# core-debug.net
KiCad netlist of a schematic drawn in EAGLE
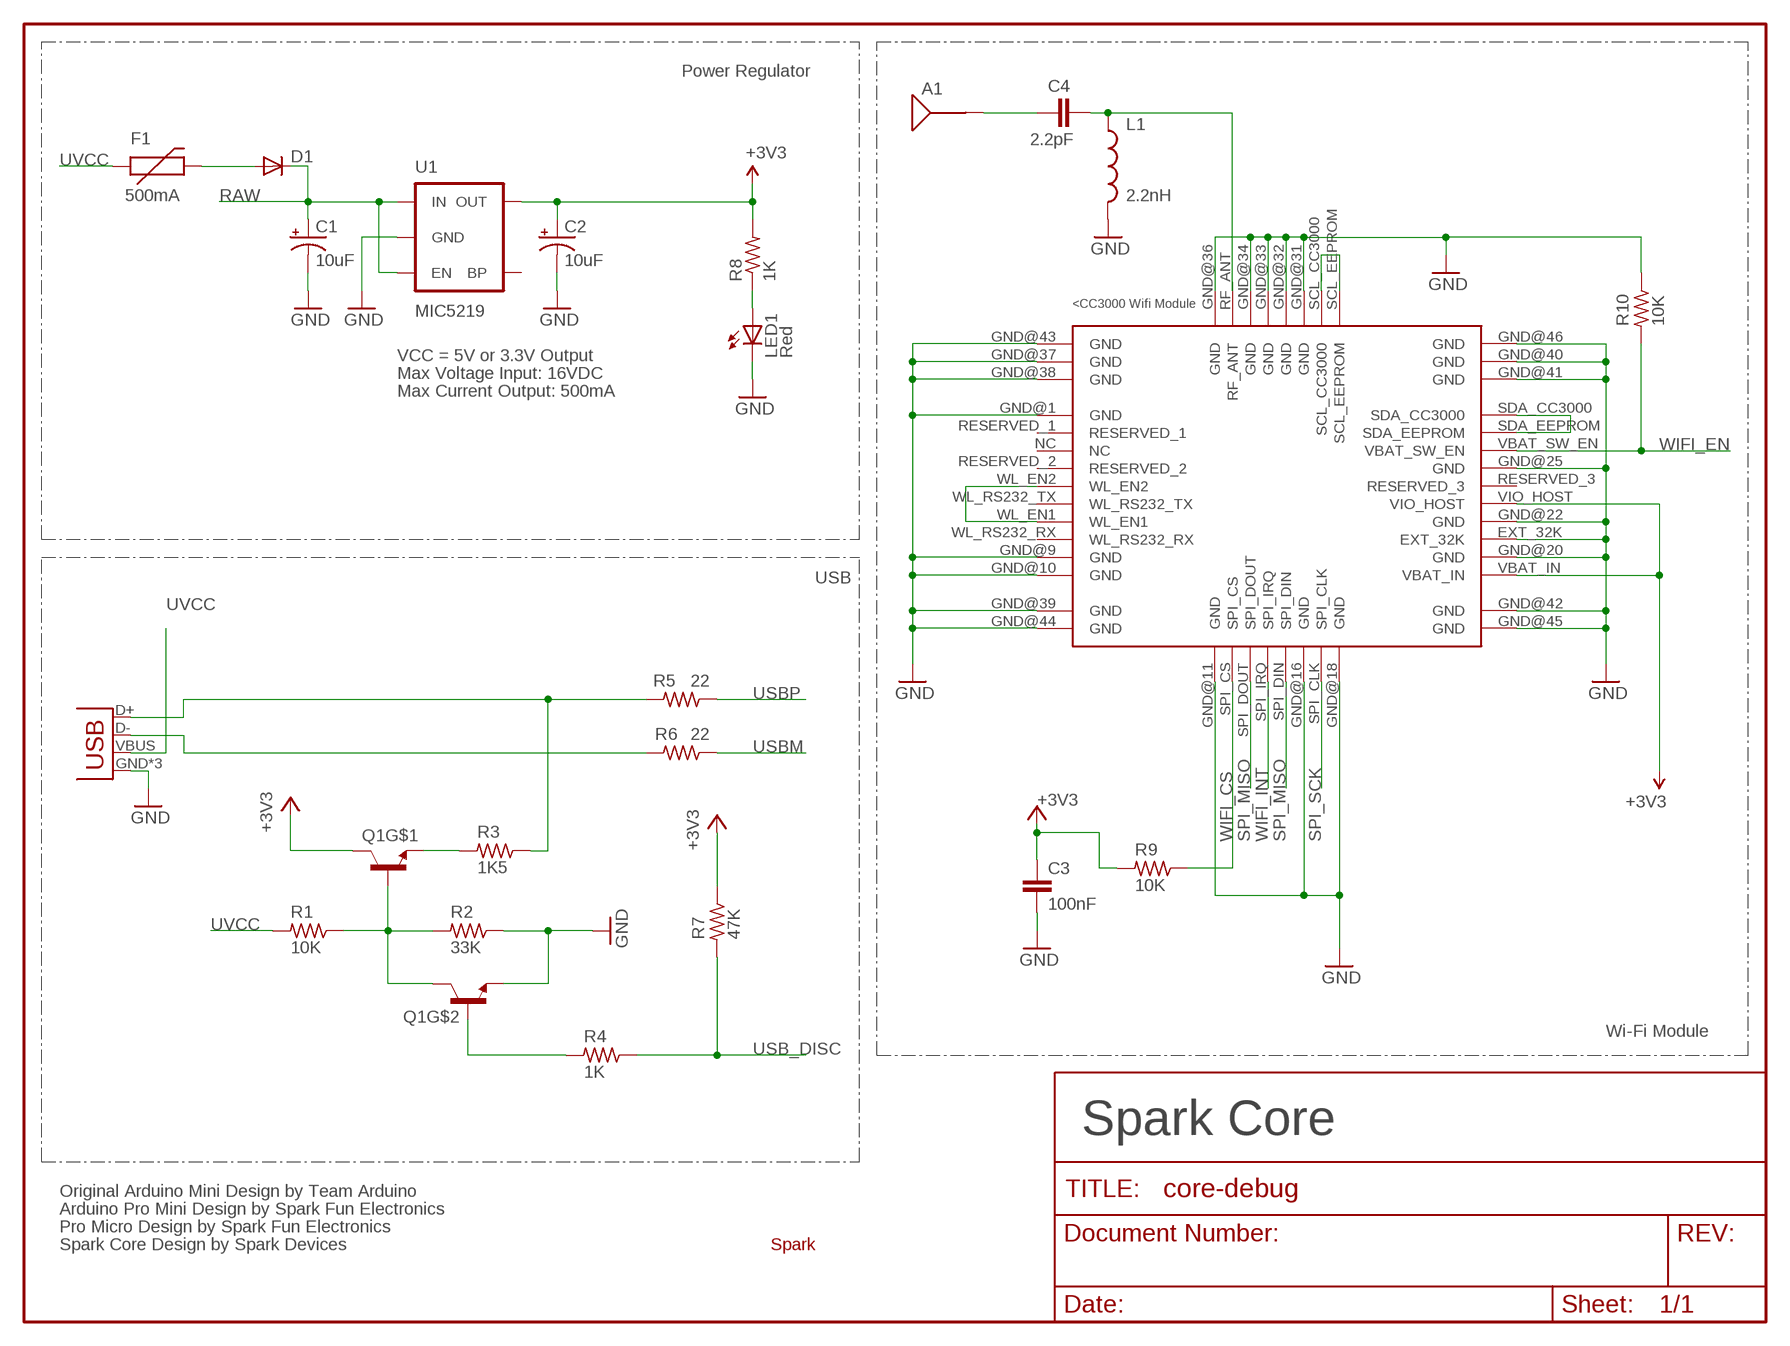
[diagram p0: schematic, sheet 1, part 1 of 2]
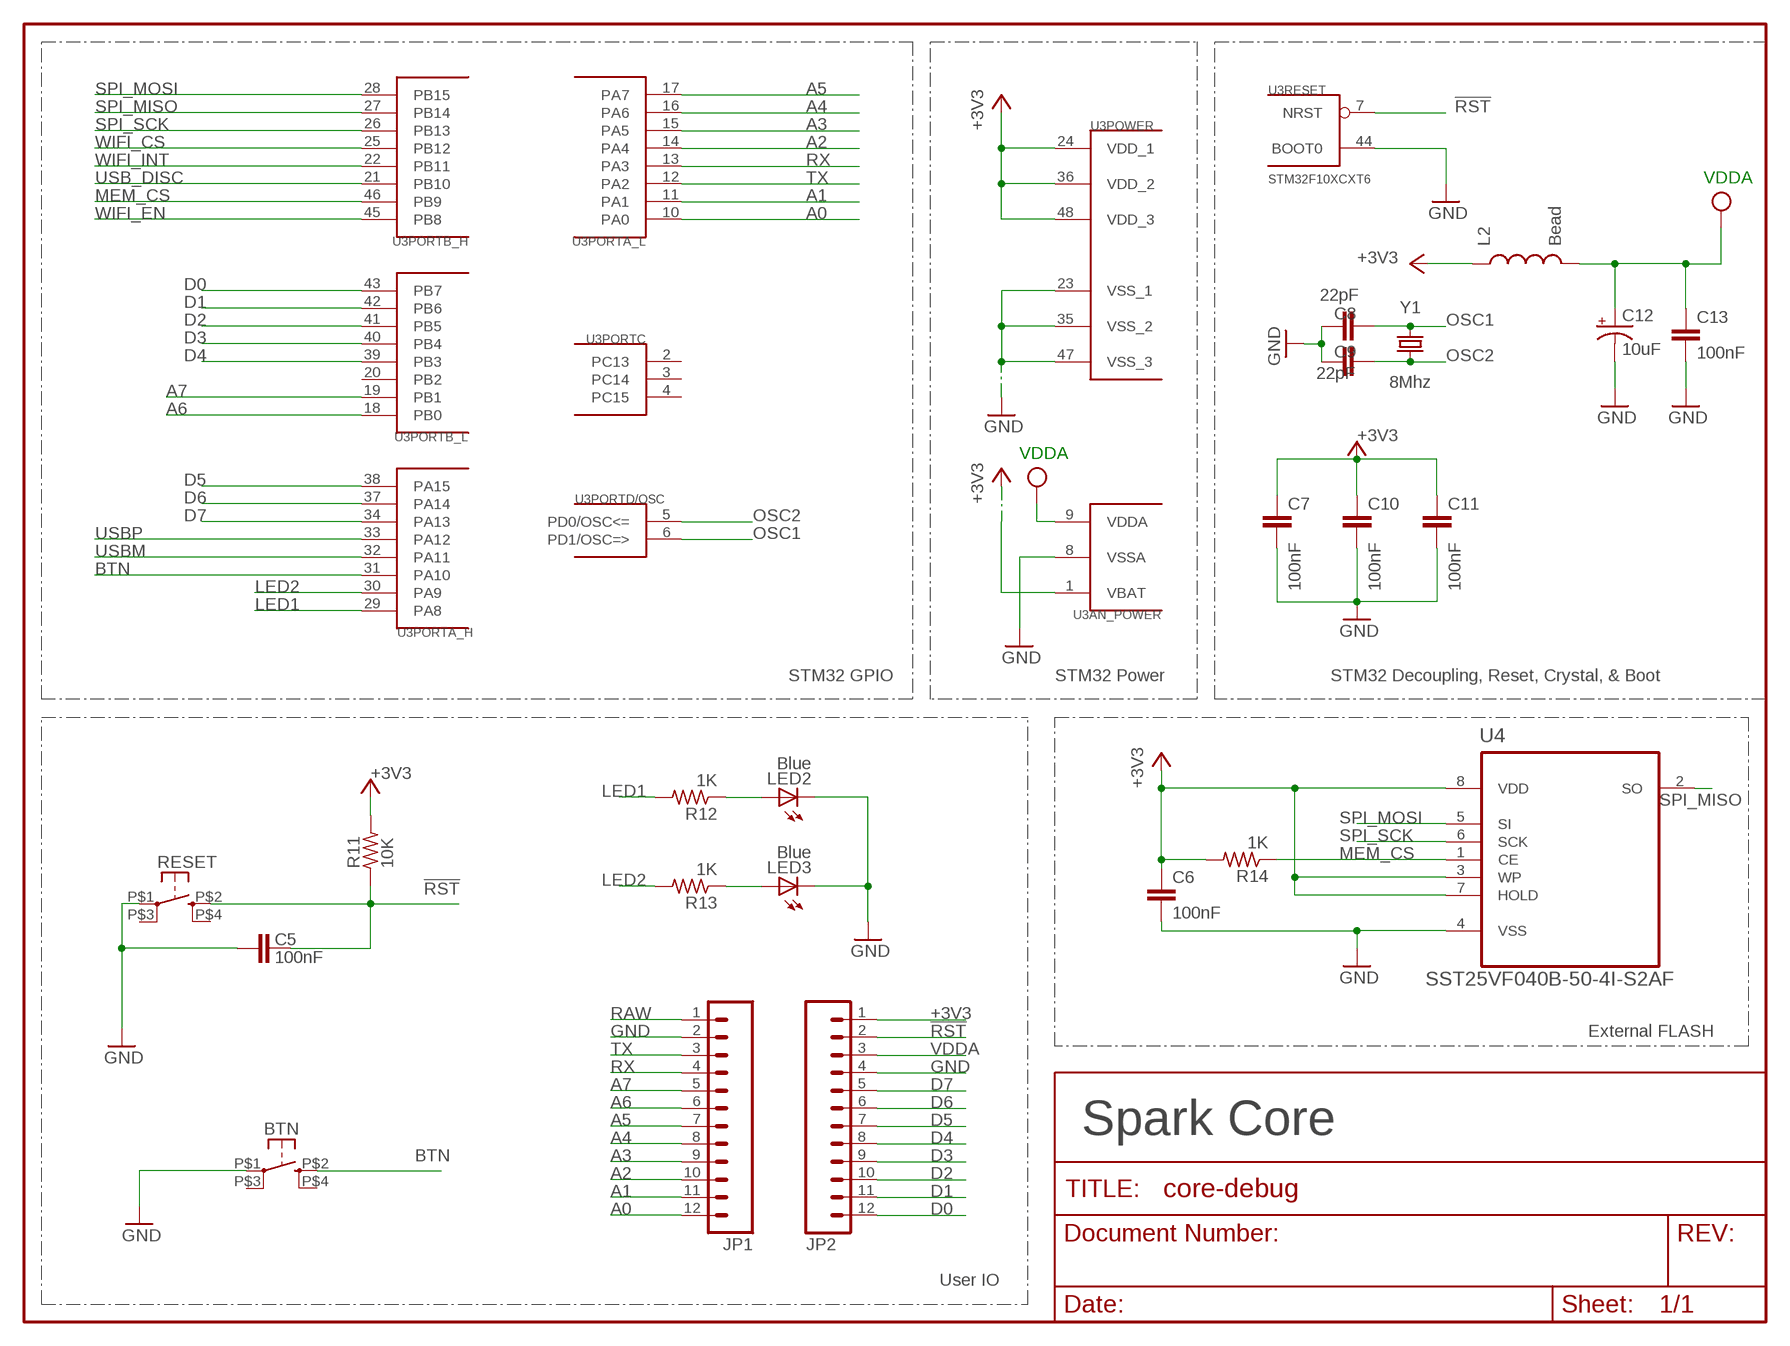
[diagram p1: schematic, sheet 1, part 2 of 2]

(export (version "E")
  (design (tool "Eeschema 10.0.6"))
  (components
    (comp (ref "A1")
      (value "ANTENNA2SMD5")
      (footprint "eagle-import:ANTENNA-CHIP5")
      (libsource (lib "eagle-import") (part "ANTENNA2SMD5"))
    )
    (comp (ref "BTN")
      (value "KMR211GLFS")
      (footprint "eagle-import:PUSHBUTTON-KMR241GLFS")
      (libsource (lib "eagle-import") (part "BUTTON-KMR241GLFS"))
    )
    (comp (ref "C1")
      (value "10uF")
      (footprint "eagle-import:EIA3216")
      (libsource (lib "eagle-import") (part "CAP_POL1206"))
    )
    (comp (ref "C2")
      (value "10uF")
      (footprint "eagle-import:EIA3216")
      (libsource (lib "eagle-import") (part "CAP_POL1206"))
    )
    (comp (ref "C3")
      (value "100nF")
      (footprint "eagle-import:C0603")
      (libsource (lib "eagle-import") (part "C-EUC0603"))
    )
    (comp (ref "C4")
      (value "2.2pF")
      (footprint "eagle-import:C0603")
      (libsource (lib "eagle-import") (part "C-EUC0603"))
    )
    (comp (ref "C5")
      (value "100nF")
      (footprint "eagle-import:C0603")
      (libsource (lib "eagle-import") (part "C-EUC0603"))
    )
    (comp (ref "C6")
      (value "100nF")
      (footprint "eagle-import:C0603")
      (libsource (lib "eagle-import") (part "C-EUC0603"))
    )
    (comp (ref "C7")
      (value "100nF")
      (footprint "eagle-import:C0603")
      (libsource (lib "eagle-import") (part "C-EUC0603"))
    )
    (comp (ref "C8")
      (value "22pF")
      (footprint "eagle-import:C0603")
      (libsource (lib "eagle-import") (part "C-EUC0603"))
    )
    (comp (ref "C9")
      (value "22pF")
      (footprint "eagle-import:C0603")
      (libsource (lib "eagle-import") (part "C-EUC0603"))
    )
    (comp (ref "C10")
      (value "100nF")
      (footprint "eagle-import:C0603")
      (libsource (lib "eagle-import") (part "C-EUC0603"))
    )
    (comp (ref "C11")
      (value "100nF")
      (footprint "eagle-import:C0603")
      (libsource (lib "eagle-import") (part "C-EUC0603"))
    )
    (comp (ref "C12")
      (value "10uF")
      (footprint "eagle-import:EIA3216")
      (libsource (lib "eagle-import") (part "CAP_POL1206"))
    )
    (comp (ref "C13")
      (value "100nF")
      (footprint "eagle-import:C0603")
      (libsource (lib "eagle-import") (part "C-EUC0603"))
    )
    (comp (ref "D1")
      (value "DIODESOD")
      (footprint "eagle-import:SOD-323")
      (libsource (lib "eagle-import") (part "DIODESOD"))
    )
    (comp (ref "F1")
      (value "500mA")
      (footprint "eagle-import:PTC-1206")
      (libsource (lib "eagle-import") (part "PTCSMD"))
    )
    (comp (ref "JP1")
      (value "M12PTH")
      (footprint "eagle-import:1X12")
      (libsource (lib "eagle-import") (part "M12PTH"))
    )
    (comp (ref "JP2")
      (value "M12PTH")
      (footprint "eagle-import:1X12")
      (libsource (lib "eagle-import") (part "M12PTH"))
    )
    (comp (ref "L1")
      (value "2.2nH")
      (footprint "eagle-import:0603")
      (libsource (lib "eagle-import") (part "INDUCTOR0603"))
    )
    (comp (ref "L2")
      (value "Bead")
      (footprint "eagle-import:0603")
      (libsource (lib "eagle-import") (part "INDUCTOR0603"))
    )
    (comp (ref "LED1")
      (value "Red")
      (footprint "eagle-import:LED-0603")
      (libsource (lib "eagle-import") (part "LED0603"))
    )
    (comp (ref "LED2")
      (value "Blue")
      (footprint "eagle-import:LED-0603")
      (libsource (lib "eagle-import") (part "LED0603"))
    )
    (comp (ref "LED3")
      (value "Blue")
      (footprint "eagle-import:LED-0603")
      (libsource (lib "eagle-import") (part "LED0603"))
    )
    (comp (ref "Q1")
      (value "MMDT3904")
      (footprint "eagle-import:SOT363")
      (libsource (lib "eagle-import") (part "MMDT3904"))
    )
    (comp (ref "R1")
      (value "10K")
      (footprint "eagle-import:R0603")
      (libsource (lib "eagle-import") (part "R-US_R0603"))
    )
    (comp (ref "R2")
      (value "33K")
      (footprint "eagle-import:R0603")
      (libsource (lib "eagle-import") (part "R-US_R0603"))
    )
    (comp (ref "R3")
      (value "1K5")
      (footprint "eagle-import:R0603")
      (libsource (lib "eagle-import") (part "R-US_R0603"))
    )
    (comp (ref "R4")
      (value "1K")
      (footprint "eagle-import:R0603")
      (libsource (lib "eagle-import") (part "R-US_R0603"))
    )
    (comp (ref "R5")
      (value "22")
      (footprint "eagle-import:R0603")
      (libsource (lib "eagle-import") (part "R-US_R0603"))
    )
    (comp (ref "R6")
      (value "22")
      (footprint "eagle-import:R0603")
      (libsource (lib "eagle-import") (part "R-US_R0603"))
    )
    (comp (ref "R7")
      (value "47K")
      (footprint "eagle-import:R0603")
      (libsource (lib "eagle-import") (part "R-US_R0603"))
    )
    (comp (ref "R8")
      (value "1K")
      (footprint "eagle-import:R0603")
      (libsource (lib "eagle-import") (part "R-US_R0603"))
    )
    (comp (ref "R9")
      (value "10K")
      (footprint "eagle-import:R0603")
      (libsource (lib "eagle-import") (part "R-US_R0603"))
    )
    (comp (ref "R10")
      (value "10K")
      (footprint "eagle-import:R0603")
      (libsource (lib "eagle-import") (part "R-US_R0603"))
    )
    (comp (ref "R11")
      (value "10K")
      (footprint "eagle-import:R0603")
      (libsource (lib "eagle-import") (part "R-US_R0603"))
    )
    (comp (ref "R12")
      (value "1K")
      (footprint "eagle-import:R0603")
      (libsource (lib "eagle-import") (part "R-US_R0603"))
    )
    (comp (ref "R13")
      (value "1K")
      (footprint "eagle-import:R0603")
      (libsource (lib "eagle-import") (part "R-US_R0603"))
    )
    (comp (ref "R14")
      (value "1K")
      (footprint "eagle-import:R0603")
      (libsource (lib "eagle-import") (part "R-US_R0603"))
    )
    (comp (ref "RESET")
      (value "KMR211GLFS")
      (footprint "eagle-import:PUSHBUTTON-KMR241GLFS")
      (libsource (lib "eagle-import") (part "BUTTON-KMR241GLFS"))
    )
    (comp (ref "U$1")
      (value "SPARK_LOGO2")
      (footprint "eagle-import:SPARK_LOGO2")
      (libsource (lib "eagle-import") (part "SPARK_LOGO2"))
    )
    (comp (ref "U1")
      (value "MIC5219")
      (footprint "eagle-import:SOT23-5")
      (libsource (lib "eagle-import") (part "V_REG_LDOSMD"))
    )
    (comp (ref "U2")
      (value "CC3000")
      (footprint "eagle-import:CC3000")
      (libsource (lib "eagle-import") (part "CC3000"))
    )
    (comp (ref "U3")
      (value "STM32F10XCXT6")
      (footprint "eagle-import:TQFP48")
      (libsource (lib "eagle-import") (part "STM32F10XCXT6"))
    )
    (comp (ref "U4")
      (value "SST25VF040B-50-4I-S2AF")
      (footprint "eagle-import:SOIC127P790X216-8N")
      (libsource (lib "eagle-import") (part "SST25VF040B-50-4I-S2AF"))
    )
    (comp (ref "X1")
      (value "USB-MICROB")
      (footprint "eagle-import:USB-MICROB")
      (libsource (lib "eagle-import") (part "USB-MICROB"))
    )
    (comp (ref "Y1")
      (value "8Mhz")
      (footprint "eagle-import:CRYSTAL-SMD-5X3")
      (libsource (lib "eagle-import") (part "CRYSTAL5X3"))
    )
  )
  (nets
    (net (code "1") (name "+3V3") (class "Default")
      (node (ref "C10") (pin "1") (pinfunction "1_1") (pintype "passive"))
      (node (ref "C11") (pin "1") (pinfunction "1_1") (pintype "passive"))
      (node (ref "C2") (pin "A") (pinfunction "+_A") (pintype "passive"))
      (node (ref "C3") (pin "1") (pinfunction "1_1") (pintype "passive"))
      (node (ref "C6") (pin "1") (pinfunction "1_1") (pintype "passive"))
      (node (ref "C7") (pin "1") (pinfunction "1_1") (pintype "passive"))
      (node (ref "JP2") (pin "1") (pinfunction "1_1") (pintype "passive"))
      (node (ref "L2") (pin "1") (pinfunction "1_1") (pintype "passive"))
      (node (ref "Q1") (pin "3") (pinfunction "C_3") (pintype "passive"))
      (node (ref "R11") (pin "2") (pinfunction "2_2") (pintype "passive"))
      (node (ref "R14") (pin "2") (pinfunction "2_2") (pintype "passive"))
      (node (ref "R7") (pin "1") (pinfunction "1_1") (pintype "passive"))
      (node (ref "R8") (pin "2") (pinfunction "2_2") (pintype "passive"))
      (node (ref "R9") (pin "2") (pinfunction "2_2") (pintype "passive"))
      (node (ref "U1") (pin "5") (pinfunction "OUT_5") (pintype "passive"))
      (node (ref "U2") (pin "VBAT_IN") (pinfunction "VBAT_IN_VBAT_IN") (pintype "power_in"))
      (node (ref "U2") (pin "VIO_HOST") (pinfunction "VIO_HOST_VIO_HOST") (pintype "power_in"))
      (node (ref "U3") (pin "1") (pinfunction "VBAT_1") (pintype "power_in"))
      (node (ref "U3") (pin "24") (pinfunction "VDD_1_24") (pintype "power_in"))
      (node (ref "U3") (pin "36") (pinfunction "VDD_2_36") (pintype "power_in"))
      (node (ref "U3") (pin "48") (pinfunction "VDD_3_48") (pintype "power_in"))
      (node (ref "U4") (pin "3") (pinfunction "WP_3") (pintype "input"))
      (node (ref "U4") (pin "7") (pinfunction "HOLD_7") (pintype "input"))
      (node (ref "U4") (pin "8") (pinfunction "VDD_8") (pintype "power_in"))
    )
    (net (code "2") (name "/A0") (class "Default")
      (node (ref "JP1") (pin "12") (pinfunction "12_12") (pintype "passive"))
      (node (ref "U3") (pin "10") (pinfunction "PA0_10") (pintype "bidirectional"))
    )
    (net (code "3") (name "/A1") (class "Default")
      (node (ref "JP1") (pin "11") (pinfunction "11_11") (pintype "passive"))
      (node (ref "U3") (pin "11") (pinfunction "PA1_11") (pintype "bidirectional"))
    )
    (net (code "4") (name "/A2") (class "Default")
      (node (ref "JP1") (pin "10") (pinfunction "10_10") (pintype "passive"))
      (node (ref "U3") (pin "14") (pinfunction "PA4_14") (pintype "bidirectional"))
    )
    (net (code "5") (name "/A3") (class "Default")
      (node (ref "JP1") (pin "9") (pinfunction "9_9") (pintype "passive"))
      (node (ref "U3") (pin "15") (pinfunction "PA5_15") (pintype "bidirectional"))
    )
    (net (code "6") (name "/A4") (class "Default")
      (node (ref "JP1") (pin "8") (pinfunction "8_8") (pintype "passive"))
      (node (ref "U3") (pin "16") (pinfunction "PA6_16") (pintype "bidirectional"))
    )
    (net (code "7") (name "/A5") (class "Default")
      (node (ref "JP1") (pin "7") (pinfunction "7_7") (pintype "passive"))
      (node (ref "U3") (pin "17") (pinfunction "PA7_17") (pintype "bidirectional"))
    )
    (net (code "8") (name "/A6") (class "Default")
      (node (ref "JP1") (pin "6") (pinfunction "6_6") (pintype "passive"))
      (node (ref "U3") (pin "18") (pinfunction "PB0_18") (pintype "bidirectional"))
    )
    (net (code "9") (name "/A7") (class "Default")
      (node (ref "JP1") (pin "5") (pinfunction "5_5") (pintype "passive"))
      (node (ref "U3") (pin "19") (pinfunction "PB1_19") (pintype "bidirectional"))
    )
    (net (code "10") (name "/BTN") (class "Default")
      (node (ref "BTN") (pin "P$2") (pinfunction "2_P$2") (pintype "passive"))
      (node (ref "U3") (pin "31") (pinfunction "PA10_31") (pintype "bidirectional"))
    )
    (net (code "11") (name "/D0") (class "Default")
      (node (ref "JP2") (pin "12") (pinfunction "12_12") (pintype "passive"))
      (node (ref "U3") (pin "43") (pinfunction "PB7_43") (pintype "bidirectional"))
    )
    (net (code "12") (name "/D1") (class "Default")
      (node (ref "JP2") (pin "11") (pinfunction "11_11") (pintype "passive"))
      (node (ref "U3") (pin "42") (pinfunction "PB6_42") (pintype "bidirectional"))
    )
    (net (code "13") (name "/D2") (class "Default")
      (node (ref "JP2") (pin "10") (pinfunction "10_10") (pintype "passive"))
      (node (ref "U3") (pin "41") (pinfunction "PB5_41") (pintype "bidirectional"))
    )
    (net (code "14") (name "/D3") (class "Default")
      (node (ref "JP2") (pin "9") (pinfunction "9_9") (pintype "passive"))
      (node (ref "U3") (pin "40") (pinfunction "PB4_40") (pintype "bidirectional"))
    )
    (net (code "15") (name "/D4") (class "Default")
      (node (ref "JP2") (pin "8") (pinfunction "8_8") (pintype "passive"))
      (node (ref "U3") (pin "39") (pinfunction "PB3_39") (pintype "bidirectional"))
    )
    (net (code "16") (name "/D5") (class "Default")
      (node (ref "JP2") (pin "7") (pinfunction "7_7") (pintype "passive"))
      (node (ref "U3") (pin "38") (pinfunction "PA15_38") (pintype "bidirectional"))
    )
    (net (code "17") (name "/D6") (class "Default")
      (node (ref "JP2") (pin "6") (pinfunction "6_6") (pintype "passive"))
      (node (ref "U3") (pin "37") (pinfunction "PA14_37") (pintype "bidirectional"))
    )
    (net (code "18") (name "/D7") (class "Default")
      (node (ref "JP2") (pin "5") (pinfunction "5_5") (pintype "passive"))
      (node (ref "U3") (pin "34") (pinfunction "PA13_34") (pintype "bidirectional"))
    )
    (net (code "19") (name "/LED1") (class "Default")
      (node (ref "R12") (pin "2") (pinfunction "2_2") (pintype "passive"))
      (node (ref "U3") (pin "29") (pinfunction "PA8_29") (pintype "bidirectional"))
    )
    (net (code "20") (name "/LED2") (class "Default")
      (node (ref "R13") (pin "2") (pinfunction "2_2") (pintype "passive"))
      (node (ref "U3") (pin "30") (pinfunction "PA9_30") (pintype "bidirectional"))
    )
    (net (code "21") (name "/MEM_CS") (class "Default")
      (node (ref "R14") (pin "1") (pinfunction "1_1") (pintype "passive"))
      (node (ref "U3") (pin "46") (pinfunction "PB9_46") (pintype "bidirectional"))
      (node (ref "U4") (pin "1") (pinfunction "CE_1") (pintype "input"))
    )
    (net (code "22") (name "/OSC1") (class "Default")
      (node (ref "C8") (pin "1") (pinfunction "1_1") (pintype "passive"))
      (node (ref "U3") (pin "6") (pinfunction "PD1/OSC=>_6") (pintype "bidirectional"))
      (node (ref "Y1") (pin "3") (pinfunction "2_3") (pintype "passive"))
    )
    (net (code "23") (name "/OSC2") (class "Default")
      (node (ref "C9") (pin "1") (pinfunction "1_1") (pintype "passive"))
      (node (ref "U3") (pin "5") (pinfunction "PD0/OSC<=_5") (pintype "bidirectional"))
      (node (ref "Y1") (pin "1") (pinfunction "1_1") (pintype "passive"))
    )
    (net (code "24") (name "/RAW") (class "Default")
      (node (ref "C1") (pin "A") (pinfunction "+_A") (pintype "passive"))
      (node (ref "D1") (pin "1") (pinfunction "C_1") (pintype "passive"))
      (node (ref "JP1") (pin "1") (pinfunction "1_1") (pintype "passive"))
      (node (ref "U1") (pin "1") (pinfunction "IN_1") (pintype "input"))
      (node (ref "U1") (pin "3") (pinfunction "EN_3") (pintype "input"))
    )
    (net (code "25") (name "/RX") (class "Default")
      (node (ref "JP1") (pin "4") (pinfunction "4_4") (pintype "passive"))
      (node (ref "U3") (pin "13") (pinfunction "PA3_13") (pintype "bidirectional"))
    )
    (net (code "26") (name "/SPI_MISO") (class "Default")
      (node (ref "U2") (pin "SPI_DIN") (pinfunction "SPI_DIN_SPI_DIN") (pintype "input"))
      (node (ref "U2") (pin "SPI_DOUT") (pinfunction "SPI_DOUT_SPI_DOUT") (pintype "output"))
      (node (ref "U3") (pin "27") (pinfunction "PB14_27") (pintype "bidirectional"))
      (node (ref "U4") (pin "2") (pinfunction "SO_2") (pintype "output"))
    )
    (net (code "27") (name "/SPI_MOSI") (class "Default")
      (node (ref "U3") (pin "28") (pinfunction "PB15_28") (pintype "bidirectional"))
      (node (ref "U4") (pin "5") (pinfunction "SI_5") (pintype "input"))
    )
    (net (code "28") (name "/SPI_SCK") (class "Default")
      (node (ref "U2") (pin "SPI_CLK") (pinfunction "SPI_CLK_SPI_CLK") (pintype "input"))
      (node (ref "U3") (pin "26") (pinfunction "PB13_26") (pintype "bidirectional"))
      (node (ref "U4") (pin "6") (pinfunction "SCK_6") (pintype "input"))
    )
    (net (code "29") (name "/TX") (class "Default")
      (node (ref "JP1") (pin "3") (pinfunction "3_3") (pintype "passive"))
      (node (ref "U3") (pin "12") (pinfunction "PA2_12") (pintype "bidirectional"))
    )
    (net (code "30") (name "/USBM") (class "Default")
      (node (ref "R6") (pin "1") (pinfunction "1_1") (pintype "passive"))
      (node (ref "U3") (pin "32") (pinfunction "PA11_32") (pintype "bidirectional"))
    )
    (net (code "31") (name "/USBP") (class "Default")
      (node (ref "R5") (pin "1") (pinfunction "1_1") (pintype "passive"))
      (node (ref "U3") (pin "33") (pinfunction "PA12_33") (pintype "bidirectional"))
    )
    (net (code "32") (name "/USB_DISC") (class "Default")
      (node (ref "R4") (pin "1") (pinfunction "1_1") (pintype "passive"))
      (node (ref "R7") (pin "2") (pinfunction "2_2") (pintype "passive"))
      (node (ref "U3") (pin "21") (pinfunction "PB10_21") (pintype "bidirectional"))
    )
    (net (code "33") (name "/UVCC") (class "Default")
      (node (ref "F1") (pin "1") (pinfunction "1_1") (pintype "bidirectional"))
      (node (ref "R1") (pin "2") (pinfunction "2_2") (pintype "passive"))
      (node (ref "X1") (pin "VBUS") (pinfunction "VBUS_VBUS") (pintype "bidirectional"))
    )
    (net (code "34") (name "/WIFI_CS") (class "Default")
      (node (ref "R9") (pin "1") (pinfunction "1_1") (pintype "passive"))
      (node (ref "U2") (pin "SPI_CS") (pinfunction "SPI_CS_SPI_CS") (pintype "input"))
      (node (ref "U3") (pin "25") (pinfunction "PB12_25") (pintype "bidirectional"))
    )
    (net (code "35") (name "/WIFI_EN") (class "Default")
      (node (ref "R10") (pin "2") (pinfunction "2_2") (pintype "passive"))
      (node (ref "U2") (pin "VBAT_SW_EN") (pinfunction "VBAT_SW_EN_VBAT_SW_EN") (pintype "input"))
      (node (ref "U3") (pin "45") (pinfunction "PB8_45") (pintype "bidirectional"))
    )
    (net (code "36") (name "/WIFI_INT") (class "Default")
      (node (ref "U2") (pin "SPI_IRQ") (pinfunction "SPI_IRQ_SPI_IRQ") (pintype "output"))
      (node (ref "U3") (pin "22") (pinfunction "PB11_22") (pintype "bidirectional"))
    )
    (net (code "37") (name "/~{RST}") (class "Default")
      (node (ref "C5") (pin "2") (pinfunction "2_2") (pintype "passive"))
      (node (ref "JP2") (pin "2") (pinfunction "2_2") (pintype "passive"))
      (node (ref "R11") (pin "1") (pinfunction "1_1") (pintype "passive"))
      (node (ref "RESET") (pin "P$2") (pinfunction "2_P$2") (pintype "passive"))
      (node (ref "U3") (pin "7") (pinfunction "NRST_7") (pintype "input"))
    )
    (net (code "38") (name "GND") (class "Default")
      (node (ref "BTN") (pin "P$1") (pinfunction "1_P$1") (pintype "passive"))
      (node (ref "C1") (pin "C") (pinfunction "-_C") (pintype "passive"))
      (node (ref "C10") (pin "2") (pinfunction "2_2") (pintype "passive"))
      (node (ref "C11") (pin "2") (pinfunction "2_2") (pintype "passive"))
      (node (ref "C12") (pin "C") (pinfunction "-_C") (pintype "passive"))
      (node (ref "C13") (pin "2") (pinfunction "2_2") (pintype "passive"))
      (node (ref "C2") (pin "C") (pinfunction "-_C") (pintype "passive"))
      (node (ref "C3") (pin "2") (pinfunction "2_2") (pintype "passive"))
      (node (ref "C5") (pin "1") (pinfunction "1_1") (pintype "passive"))
      (node (ref "C6") (pin "2") (pinfunction "2_2") (pintype "passive"))
      (node (ref "C7") (pin "2") (pinfunction "2_2") (pintype "passive"))
      (node (ref "C8") (pin "2") (pinfunction "2_2") (pintype "passive"))
      (node (ref "C9") (pin "2") (pinfunction "2_2") (pintype "passive"))
      (node (ref "JP1") (pin "2") (pinfunction "2_2") (pintype "passive"))
      (node (ref "JP2") (pin "4") (pinfunction "4_4") (pintype "passive"))
      (node (ref "L1") (pin "2") (pinfunction "2_2") (pintype "passive"))
      (node (ref "LED1") (pin "C") (pinfunction "C_C") (pintype "passive"))
      (node (ref "LED2") (pin "C") (pinfunction "C_C") (pintype "passive"))
      (node (ref "LED3") (pin "C") (pinfunction "C_C") (pintype "passive"))
      (node (ref "Q1") (pin "1") (pinfunction "E_1") (pintype "passive"))
      (node (ref "R10") (pin "1") (pinfunction "1_1") (pintype "passive"))
      (node (ref "R2") (pin "1") (pinfunction "1_1") (pintype "passive"))
      (node (ref "RESET") (pin "P$1") (pinfunction "1_P$1") (pintype "passive"))
      (node (ref "U1") (pin "2") (pinfunction "GND_2") (pintype "input"))
      (node (ref "U2") (pin "EXT_32K") (pinfunction "EXT_32K_EXT_32K") (pintype "bidirectional"))
      (node (ref "U2") (pin "GND@1") (pinfunction "GND_GND@1") (pintype "power_in"))
      (node (ref "U2") (pin "GND@10") (pinfunction "GND_GND@10") (pintype "power_in"))
      (node (ref "U2") (pin "GND@11") (pinfunction "GND_GND@11") (pintype "power_in"))
      (node (ref "U2") (pin "GND@16") (pinfunction "GND_GND@16") (pintype "power_in"))
      (node (ref "U2") (pin "GND@18") (pinfunction "GND_GND@18") (pintype "power_in"))
      (node (ref "U2") (pin "GND@20") (pinfunction "GND_GND@20") (pintype "power_in"))
      (node (ref "U2") (pin "GND@22") (pinfunction "GND_GND@22") (pintype "power_in"))
      (node (ref "U2") (pin "GND@25") (pinfunction "GND_GND@25") (pintype "power_in"))
      (node (ref "U2") (pin "GND@31") (pinfunction "GND_GND@31") (pintype "power_in"))
      (node (ref "U2") (pin "GND@32") (pinfunction "GND_GND@32") (pintype "power_in"))
      (node (ref "U2") (pin "GND@33") (pinfunction "GND_GND@33") (pintype "power_in"))
      (node (ref "U2") (pin "GND@34") (pinfunction "GND_GND@34") (pintype "power_in"))
      (node (ref "U2") (pin "GND@36") (pinfunction "GND_GND@36") (pintype "power_in"))
      (node (ref "U2") (pin "GND@37") (pinfunction "GND_GND@37") (pintype "power_in"))
      (node (ref "U2") (pin "GND@38") (pinfunction "GND_GND@38") (pintype "power_in"))
      (node (ref "U2") (pin "GND@39") (pinfunction "GND_GND@39") (pintype "power_in"))
      (node (ref "U2") (pin "GND@40") (pinfunction "GND_GND@40") (pintype "power_in"))
      (node (ref "U2") (pin "GND@41") (pinfunction "GND_GND@41") (pintype "power_in"))
      (node (ref "U2") (pin "GND@42") (pinfunction "GND_GND@42") (pintype "power_in"))
      (node (ref "U2") (pin "GND@43") (pinfunction "GND_GND@43") (pintype "power_in"))
      (node (ref "U2") (pin "GND@44") (pinfunction "GND_GND@44") (pintype "power_in"))
      (node (ref "U2") (pin "GND@45") (pinfunction "GND_GND@45") (pintype "power_in"))
      (node (ref "U2") (pin "GND@46") (pinfunction "GND_GND@46") (pintype "power_in"))
      (node (ref "U2") (pin "GND@9") (pinfunction "GND_GND@9") (pintype "power_in"))
      (node (ref "U3") (pin "23") (pinfunction "VSS_1_23") (pintype "power_in"))
      (node (ref "U3") (pin "35") (pinfunction "VSS_2_35") (pintype "power_in"))
      (node (ref "U3") (pin "44") (pinfunction "BOOT0_44") (pintype "input"))
      (node (ref "U3") (pin "47") (pinfunction "VSS_3_47") (pintype "power_in"))
      (node (ref "U3") (pin "8") (pinfunction "VSSA_8") (pintype "power_in"))
      (node (ref "U4") (pin "4") (pinfunction "VSS_4") (pintype "passive"))
      (node (ref "X1") (pin "GND") (pinfunction "GND_GND") (pintype "bidirectional"))
      (node (ref "X1") (pin "MT1") (pinfunction "GND_MT1") (pintype "bidirectional"))
      (node (ref "X1") (pin "MT2") (pinfunction "GND_MT2") (pintype "bidirectional"))
    )
    (net (code "39") (name "Net-(A1-SIGNAL)") (class "Default")
      (node (ref "A1") (pin "FEED") (pinfunction "SIGNAL_FEED") (pintype "bidirectional"))
      (node (ref "C4") (pin "1") (pinfunction "1_1") (pintype "passive"))
    )
    (net (code "40") (name "Net-(C4-Pad2)") (class "Default")
      (node (ref "C4") (pin "2") (pinfunction "2_2") (pintype "passive"))
      (node (ref "L1") (pin "1") (pinfunction "1_1") (pintype "passive"))
      (node (ref "U2") (pin "RF_ANT") (pinfunction "RF_ANT_RF_ANT") (pintype "bidirectional"))
    )
    (net (code "41") (name "Net-(D1-A)") (class "Default")
      (node (ref "D1") (pin "2") (pinfunction "A_2") (pintype "passive"))
      (node (ref "F1") (pin "2") (pinfunction "2_2") (pintype "bidirectional"))
    )
    (net (code "42") (name "Net-(LED1-PadA)") (class "Default")
      (node (ref "LED1") (pin "A") (pinfunction "A_A") (pintype "passive"))
      (node (ref "R8") (pin "1") (pinfunction "1_1") (pintype "passive"))
    )
    (net (code "43") (name "Net-(LED2-PadA)") (class "Default")
      (node (ref "LED2") (pin "A") (pinfunction "A_A") (pintype "passive"))
      (node (ref "R12") (pin "1") (pinfunction "1_1") (pintype "passive"))
    )
    (net (code "44") (name "Net-(LED3-PadA)") (class "Default")
      (node (ref "LED3") (pin "A") (pinfunction "A_A") (pintype "passive"))
      (node (ref "R13") (pin "1") (pinfunction "1_1") (pintype "passive"))
    )
    (net (code "45") (name "Net-(Q1A-B)") (class "Default")
      (node (ref "Q1") (pin "5") (pinfunction "B_5") (pintype "passive"))
      (node (ref "Q1") (pin "6") (pinfunction "C_6") (pintype "passive"))
      (node (ref "R1") (pin "1") (pinfunction "1_1") (pintype "passive"))
      (node (ref "R2") (pin "2") (pinfunction "2_2") (pintype "passive"))
    )
    (net (code "46") (name "Net-(Q1A-E)") (class "Default")
      (node (ref "Q1") (pin "4") (pinfunction "E_4") (pintype "passive"))
      (node (ref "R3") (pin "2") (pinfunction "2_2") (pintype "passive"))
    )
    (net (code "47") (name "Net-(Q1B-B)") (class "Default")
      (node (ref "Q1") (pin "2") (pinfunction "B_2") (pintype "passive"))
      (node (ref "R4") (pin "2") (pinfunction "2_2") (pintype "passive"))
    )
    (net (code "48") (name "Net-(R3-Pad1)") (class "Default")
      (node (ref "R3") (pin "1") (pinfunction "1_1") (pintype "passive"))
      (node (ref "R5") (pin "2") (pinfunction "2_2") (pintype "passive"))
      (node (ref "X1") (pin "D+") (pinfunction "D+_D+") (pintype "bidirectional"))
    )
    (net (code "49") (name "Net-(R6-Pad2)") (class "Default")
      (node (ref "R6") (pin "2") (pinfunction "2_2") (pintype "passive"))
      (node (ref "X1") (pin "D-") (pinfunction "D-_D-") (pintype "bidirectional"))
    )
    (net (code "50") (name "Net-(U2-PadSCL_CC3000)") (class "Default")
      (node (ref "U2") (pin "SCL_CC3000") (pinfunction "SCL_CC3000_SCL_CC3000") (pintype "bidirectional"))
      (node (ref "U2") (pin "SCL_EEPROM") (pinfunction "SCL_EEPROM_SCL_EEPROM") (pintype "bidirectional"))
    )
    (net (code "51") (name "Net-(U2-PadSDA_CC3000)") (class "Default")
      (node (ref "U2") (pin "SDA_CC3000") (pinfunction "SDA_CC3000_SDA_CC3000") (pintype "bidirectional"))
      (node (ref "U2") (pin "SDA_EEPROM") (pinfunction "SDA_EEPROM_SDA_EEPROM") (pintype "bidirectional"))
    )
    (net (code "52") (name "Net-(U2-PadWL_EN1)") (class "Default")
      (node (ref "U2") (pin "WL_EN1") (pinfunction "WL_EN1_WL_EN1") (pintype "input"))
      (node (ref "U2") (pin "WL_EN2") (pinfunction "WL_EN2_WL_EN2") (pintype "input"))
    )
    (net (code "53") (name "VCC") (class "Default")
      (node (ref "C12") (pin "A") (pinfunction "+_A") (pintype "passive"))
      (node (ref "C13") (pin "1") (pinfunction "1_1") (pintype "passive"))
      (node (ref "JP2") (pin "3") (pinfunction "3_3") (pintype "passive"))
      (node (ref "L2") (pin "2") (pinfunction "2_2") (pintype "passive"))
      (node (ref "U3") (pin "9") (pinfunction "VDDA_9") (pintype "power_in"))
    )
    (net (code "54") (name "unconnected-(BTN-3-PadP$3)") (class "Default")
      (node (ref "BTN") (pin "P$3") (pinfunction "3_P$3") (pintype "passive"))
    )
    (net (code "55") (name "unconnected-(BTN-4-PadP$4)") (class "Default")
      (node (ref "BTN") (pin "P$4") (pinfunction "4_P$4") (pintype "passive"))
    )
    (net (code "56") (name "unconnected-(RESET-3-PadP$3)") (class "Default")
      (node (ref "RESET") (pin "P$3") (pinfunction "3_P$3") (pintype "passive"))
    )
    (net (code "57") (name "unconnected-(RESET-4-PadP$4)") (class "Default")
      (node (ref "RESET") (pin "P$4") (pinfunction "4_P$4") (pintype "passive"))
    )
    (net (code "58") (name "unconnected-(U1-BP-Pad4)") (class "Default")
      (node (ref "U1") (pin "4") (pinfunction "BP_4") (pintype "input"))
    )
    (net (code "59") (name "unconnected-(U2-PadNC)") (class "Default")
      (node (ref "U2") (pin "NC") (pinfunction "NC_NC") (pintype "no_connect"))
    )
    (net (code "60") (name "unconnected-(U2-PadRESERVED_1)") (class "Default")
      (node (ref "U2") (pin "RESERVED_1") (pinfunction "RESERVED_1_RESERVED_1") (pintype "bidirectional"))
    )
    (net (code "61") (name "unconnected-(U2-PadRESERVED_2)") (class "Default")
      (node (ref "U2") (pin "RESERVED_2") (pinfunction "RESERVED_2_RESERVED_2") (pintype "bidirectional"))
    )
    (net (code "62") (name "unconnected-(U2-PadRESERVED_3)") (class "Default")
      (node (ref "U2") (pin "RESERVED_3") (pinfunction "RESERVED_3_RESERVED_3") (pintype "bidirectional"))
    )
    (net (code "63") (name "unconnected-(U2-PadWL_RS232_RX)") (class "Default")
      (node (ref "U2") (pin "WL_RS232_RX") (pinfunction "WL_RS232_RX_WL_RS232_RX") (pintype "input"))
    )
    (net (code "64") (name "unconnected-(U2-PadWL_RS232_TX)") (class "Default")
      (node (ref "U2") (pin "WL_RS232_TX") (pinfunction "WL_RS232_TX_WL_RS232_TX") (pintype "output"))
    )
    (net (code "65") (name "unconnected-(U3E-PB2-Pad20)") (class "Default")
      (node (ref "U3") (pin "20") (pinfunction "PB2_20") (pintype "bidirectional"))
    )
    (net (code "66") (name "unconnected-(U3F-PC13-Pad2)") (class "Default")
      (node (ref "U3") (pin "2") (pinfunction "PC13_2") (pintype "bidirectional"))
    )
    (net (code "67") (name "unconnected-(U3F-PC14-Pad3)") (class "Default")
      (node (ref "U3") (pin "3") (pinfunction "PC14_3") (pintype "bidirectional"))
    )
    (net (code "68") (name "unconnected-(U3F-PC15-Pad4)") (class "Default")
      (node (ref "U3") (pin "4") (pinfunction "PC15_4") (pintype "bidirectional"))
    )
  )
)
